# PS.net
KiCad netlist of a schematic drawn in Altium Designer
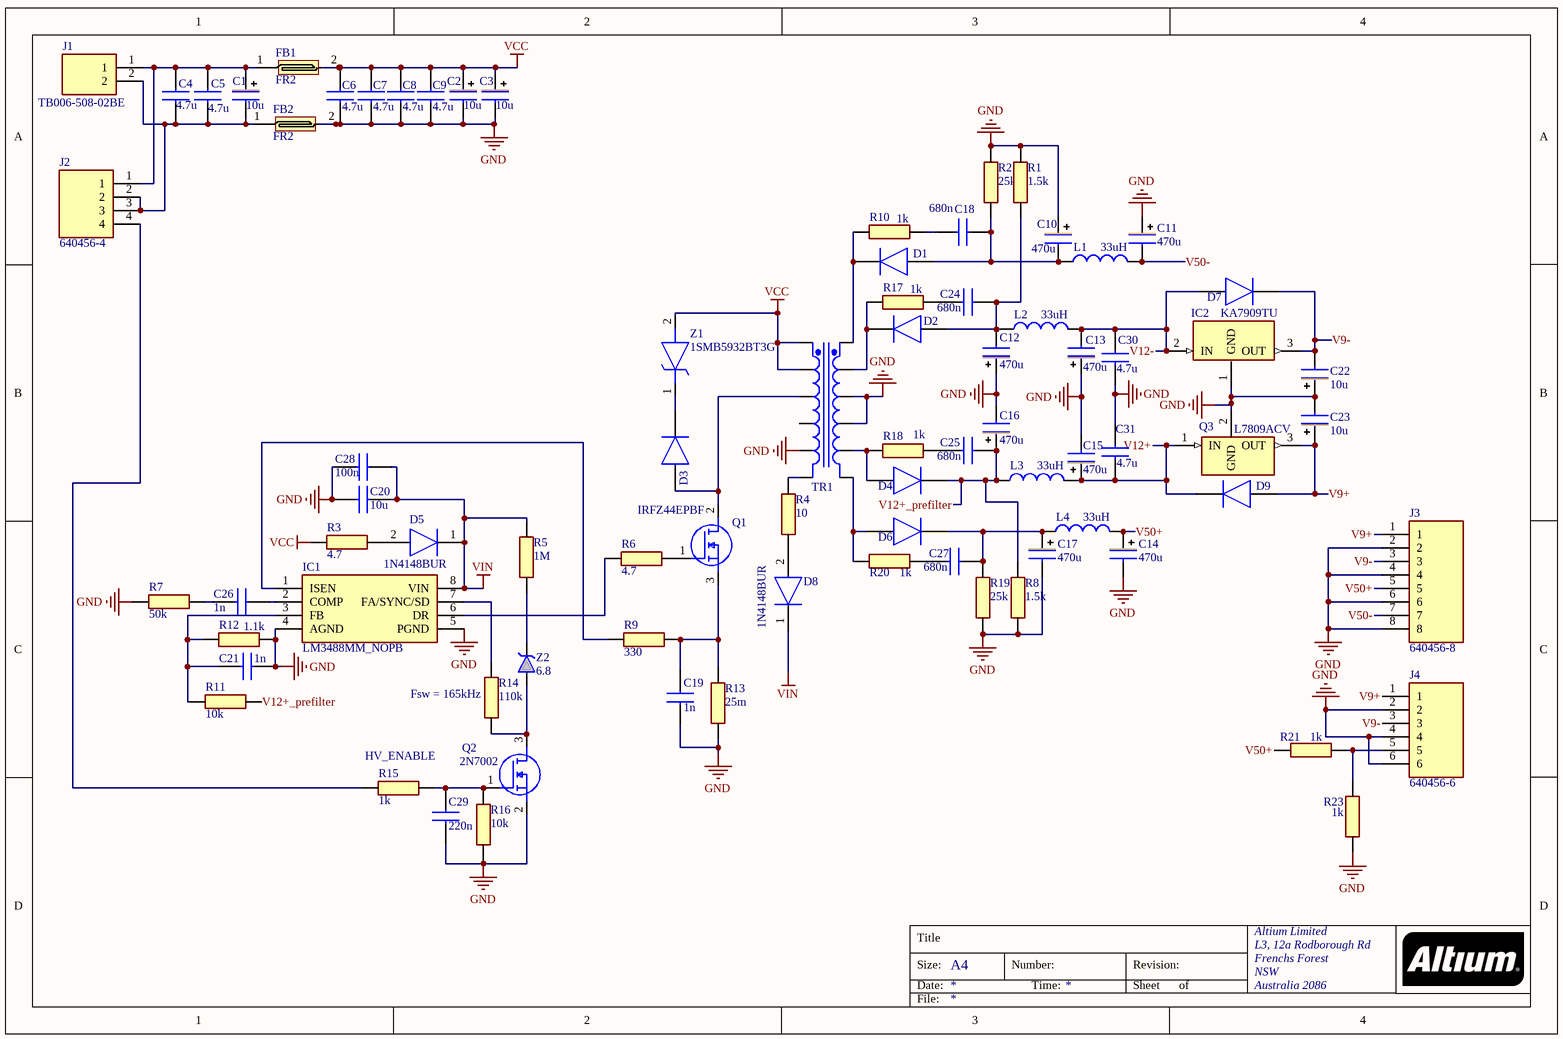
[diagram p0: PS.SchDoc]

(export (version "E")
  (design (tool "Eeschema 10.0.6"))
  (components
    (comp (ref "C1")
      (value "10u")
      (footprint "CapPol8mm")
      (description "Capacitor polarized electrolytic")
      (fields
        (field (name "MANUFACTURER_PART_NUMBER") "B43640A9477M")
        (field (name "MOUSER PART NUMBER") "871-B43640A9477M")
      )
      (libsource (lib "Schlib") (part "CapPol"))
    )
    (comp (ref "C2")
      (value "10u")
      (footprint "CapPol8mm")
      (description "Capacitor polarized electrolytic")
      (fields
        (field (name "MANUFACTURER_PART_NUMBER") "B43640A9477M")
        (field (name "MOUSER PART NUMBER") "871-B43640A9477M")
      )
      (libsource (lib "Schlib") (part "CapPol"))
    )
    (comp (ref "C3")
      (value "10u")
      (footprint "CapPol8mm")
      (description "Capacitor polarized electrolytic")
      (fields
        (field (name "MANUFACTURER_PART_NUMBER") "B43640A9477M")
        (field (name "MOUSER PART NUMBER") "871-B43640A9477M")
      )
      (libsource (lib "Schlib") (part "CapPol"))
    )
    (comp (ref "C4")
      (value "4.7u")
      (footprint "CAPC2012X140N")
      (description "Capacitor smd ceramic")
      (fields
        (field (name "MANUFACTURER_PART_NUMBER") "C3216C0G1H562J060AA")
        (field (name "Comment") "Capacitor_SMD")
      )
      (libsource (lib "Schlib") (part "Capacitor_SMD"))
    )
    (comp (ref "C5")
      (value "4.7u")
      (footprint "CAPC2012X140N")
      (description "Capacitor smd ceramic")
      (fields
        (field (name "MANUFACTURER_PART_NUMBER") "C3216C0G1H562J060AA")
        (field (name "Comment") "Capacitor_SMD")
      )
      (libsource (lib "Schlib") (part "Capacitor_SMD"))
    )
    (comp (ref "C6")
      (value "4.7u")
      (footprint "CAPC2012X140N")
      (description "Capacitor smd ceramic")
      (fields
        (field (name "MANUFACTURER_PART_NUMBER") "C3216C0G1H562J060AA")
        (field (name "Comment") "Capacitor_SMD")
      )
      (libsource (lib "Schlib") (part "Capacitor_SMD"))
    )
    (comp (ref "C7")
      (value "4.7u")
      (footprint "CAPC2012X140N")
      (description "Capacitor smd ceramic")
      (fields
        (field (name "MANUFACTURER_PART_NUMBER") "C3216C0G1H562J060AA")
        (field (name "Comment") "Capacitor_SMD")
      )
      (libsource (lib "Schlib") (part "Capacitor_SMD"))
    )
    (comp (ref "C8")
      (value "4.7u")
      (footprint "CAPC2012X140N")
      (description "Capacitor smd ceramic")
      (fields
        (field (name "MANUFACTURER_PART_NUMBER") "C3216C0G1H562J060AA")
        (field (name "Comment") "Capacitor_SMD")
      )
      (libsource (lib "Schlib") (part "Capacitor_SMD"))
    )
    (comp (ref "C9")
      (value "4.7u")
      (footprint "CAPC2012X140N")
      (description "Capacitor smd ceramic")
      (fields
        (field (name "MANUFACTURER_PART_NUMBER") "C3216C0G1H562J060AA")
        (field (name "Comment") "Capacitor_SMD")
      )
      (libsource (lib "Schlib") (part "Capacitor_SMD"))
    )
    (comp (ref "C10")
      (value "470u")
      (footprint "Cap_pol_5x13")
      (description "Capacitor polarized electrolytic")
      (fields
        (field (name "MANUFACTURER_PART_NUMBER") "B43640A9477M")
        (field (name "MOUSER PART NUMBER") "871-B43640A9477M")
      )
      (libsource (lib "Schlib") (part "CapPol"))
    )
    (comp (ref "C11")
      (value "470u")
      (footprint "Cap_pol_5x13")
      (description "Capacitor polarized electrolytic")
      (fields
        (field (name "MANUFACTURER_PART_NUMBER") "B43640A9477M")
        (field (name "MOUSER PART NUMBER") "871-B43640A9477M")
      )
      (libsource (lib "Schlib") (part "CapPol"))
    )
    (comp (ref "C12")
      (value "470u")
      (footprint "CapPol_D10H16")
      (description "Capacitor polarized electrolytic")
      (fields
        (field (name "MANUFACTURER_PART_NUMBER") "B43640A9477M")
        (field (name "MOUSER PART NUMBER") "871-B43640A9477M")
      )
      (libsource (lib "Schlib") (part "CapPol"))
    )
    (comp (ref "C13")
      (value "470u")
      (footprint "CapPol_D10H16")
      (description "Capacitor polarized electrolytic")
      (fields
        (field (name "MANUFACTURER_PART_NUMBER") "B43640A9477M")
        (field (name "MOUSER PART NUMBER") "871-B43640A9477M")
      )
      (libsource (lib "Schlib") (part "CapPol"))
    )
    (comp (ref "C14")
      (value "470u")
      (footprint "Cap_pol_5x13")
      (description "Capacitor polarized electrolytic")
      (fields
        (field (name "MANUFACTURER_PART_NUMBER") "B43640A9477M")
        (field (name "MOUSER PART NUMBER") "871-B43640A9477M")
      )
      (libsource (lib "Schlib") (part "CapPol"))
    )
    (comp (ref "C15")
      (value "470u")
      (footprint "CapPol_D10H16")
      (description "Capacitor polarized electrolytic")
      (fields
        (field (name "MANUFACTURER_PART_NUMBER") "B43640A9477M")
        (field (name "MOUSER PART NUMBER") "871-B43640A9477M")
      )
      (libsource (lib "Schlib") (part "CapPol"))
    )
    (comp (ref "C16")
      (value "470u")
      (footprint "CapPol_D10H16")
      (description "Capacitor polarized electrolytic")
      (fields
        (field (name "MANUFACTURER_PART_NUMBER") "B43640A9477M")
        (field (name "MOUSER PART NUMBER") "871-B43640A9477M")
      )
      (libsource (lib "Schlib") (part "CapPol"))
    )
    (comp (ref "C17")
      (value "470u")
      (footprint "Cap_pol_5x13")
      (description "Capacitor polarized electrolytic")
      (fields
        (field (name "MANUFACTURER_PART_NUMBER") "B43640A9477M")
        (field (name "MOUSER PART NUMBER") "871-B43640A9477M")
      )
      (libsource (lib "Schlib") (part "CapPol"))
    )
    (comp (ref "C18")
      (value "680n")
      (footprint "CAPC3216X95N")
      (description "Capacitor smd ceramic")
      (fields
        (field (name "MANUFACTURER_PART_NUMBER") "C3216C0G1H562J060AA")
        (field (name "Comment") "Capacitor_SMD")
      )
      (libsource (lib "Schlib") (part "Capacitor_SMD"))
    )
    (comp (ref "C19")
      (value "1n")
      (footprint "CAPC2012X140N")
      (description "Capacitor smd ceramic")
      (fields
        (field (name "MANUFACTURER_PART_NUMBER") "C3216C0G1H562J060AA")
        (field (name "Comment") "Capacitor_SMD")
      )
      (libsource (lib "Schlib") (part "Capacitor_SMD"))
    )
    (comp (ref "C20")
      (value "10u")
      (footprint "CAPC2012X140N")
      (description "Capacitor smd ceramic")
      (fields
        (field (name "MANUFACTURER_PART_NUMBER") "C3216C0G1H562J060AA")
        (field (name "Comment") "Capacitor_SMD")
      )
      (libsource (lib "Schlib") (part "Capacitor_SMD"))
    )
    (comp (ref "C21")
      (value "1n")
      (footprint "CAPC2012X140N")
      (description "Capacitor smd ceramic")
      (fields
        (field (name "MANUFACTURER_PART_NUMBER") "C3216C0G1H562J060AA")
        (field (name "Comment") "Capacitor_SMD")
      )
      (libsource (lib "Schlib") (part "Capacitor_SMD"))
    )
    (comp (ref "C22")
      (value "10u")
      (footprint "CapPol_D10H16")
      (description "Capacitor polarized electrolytic")
      (fields
        (field (name "MANUFACTURER_PART_NUMBER") "B43640A9477M")
        (field (name "MOUSER PART NUMBER") "871-B43640A9477M")
      )
      (libsource (lib "Schlib") (part "CapPol"))
    )
    (comp (ref "C23")
      (value "10u")
      (footprint "CapPol_D10H16")
      (description "Capacitor polarized electrolytic")
      (fields
        (field (name "MANUFACTURER_PART_NUMBER") "B43640A9477M")
        (field (name "MOUSER PART NUMBER") "871-B43640A9477M")
      )
      (libsource (lib "Schlib") (part "CapPol"))
    )
    (comp (ref "C24")
      (value "680n")
      (footprint "CAPC3216X95N")
      (description "Capacitor smd ceramic")
      (fields
        (field (name "MANUFACTURER_PART_NUMBER") "C3216C0G1H562J060AA")
        (field (name "Comment") "Capacitor_SMD")
      )
      (libsource (lib "Schlib") (part "Capacitor_SMD"))
    )
    (comp (ref "C25")
      (value "680n")
      (footprint "CAPC3216X95N")
      (description "Capacitor smd ceramic")
      (fields
        (field (name "MANUFACTURER_PART_NUMBER") "C3216C0G1H562J060AA")
        (field (name "Comment") "Capacitor_SMD")
      )
      (libsource (lib "Schlib") (part "Capacitor_SMD"))
    )
    (comp (ref "C26")
      (value "1n")
      (footprint "CAPC2012X140N")
      (description "Capacitor smd ceramic")
      (fields
        (field (name "MANUFACTURER_PART_NUMBER") "C3216C0G1H562J060AA")
        (field (name "Comment") "Capacitor_SMD")
      )
      (libsource (lib "Schlib") (part "Capacitor_SMD"))
    )
    (comp (ref "C27")
      (value "680n")
      (footprint "CAPC3216X95N")
      (description "Capacitor smd ceramic")
      (fields
        (field (name "MANUFACTURER_PART_NUMBER") "C3216C0G1H562J060AA")
        (field (name "Comment") "Capacitor_SMD")
      )
      (libsource (lib "Schlib") (part "Capacitor_SMD"))
    )
    (comp (ref "C28")
      (value "100n")
      (footprint "CAPC2012X140N")
      (description "Capacitor smd ceramic")
      (fields
        (field (name "MANUFACTURER_PART_NUMBER") "C3216C0G1H562J060AA")
        (field (name "Comment") "Capacitor_SMD")
      )
      (libsource (lib "Schlib") (part "Capacitor_SMD"))
    )
    (comp (ref "C29")
      (value "220n")
      (footprint "CAPC2012X140N")
      (description "Capacitor smd ceramic")
      (fields
        (field (name "MANUFACTURER_PART_NUMBER") "C3216C0G1H562J060AA")
        (field (name "Comment") "Capacitor_SMD")
      )
      (libsource (lib "Schlib") (part "Capacitor_SMD"))
    )
    (comp (ref "C30")
      (value "4.7u")
      (footprint "CAPC3216X95N")
      (description "Capacitor smd ceramic")
      (fields
        (field (name "MANUFACTURER_PART_NUMBER") "C3216C0G1H562J060AA")
        (field (name "Comment") "Capacitor_SMD")
      )
      (libsource (lib "Schlib") (part "Capacitor_SMD"))
    )
    (comp (ref "C31")
      (value "4.7u")
      (footprint "CAPC3216X95N")
      (description "Capacitor smd ceramic")
      (fields
        (field (name "MANUFACTURER_PART_NUMBER") "C3216C0G1H562J060AA")
        (field (name "Comment") "Capacitor_SMD")
      )
      (libsource (lib "Schlib") (part "Capacitor_SMD"))
    )
    (comp (ref "D1")
      (value "SS1200-LTP")
      (footprint "PcbLib:DIOM5226X244N")
      (description "Diode")
      (fields (field (name "MOUSER PART NUMBER") "833-SS1200-LTP"))
      (libsource (lib "Schlib") (part "SS1200-LTP"))
    )
    (comp (ref "D2")
      (value "S2B-13-F")
      (footprint "PcbLib:DIOM5336X250N")
      (description "Diode")
      (fields (field (name "MOUSER PART NUMBER") "621-S2B-F"))
      (libsource (lib "Schlib") (part "S2B-13-F"))
    )
    (comp (ref "D3")
      (value "SS1200-LTP")
      (footprint "PcbLib:DIOM5226X244N")
      (description "Diode")
      (fields (field (name "MOUSER PART NUMBER") "833-SS1200-LTP"))
      (libsource (lib "Schlib") (part "SS1200-LTP"))
    )
    (comp (ref "D4")
      (value "S2B-13-F")
      (footprint "PcbLib:DIOM5336X250N")
      (description "Diode")
      (fields (field (name "MOUSER PART NUMBER") "621-S2B-F"))
      (libsource (lib "Schlib") (part "S2B-13-F"))
    )
    (comp (ref "D5")
      (value "1N4148BUR")
      (footprint "PcbLib:1N4148BUR")
      (description "Diode")
      (libsource (lib "Schlib") (part "1N4148BUR"))
    )
    (comp (ref "D6")
      (value "SS1200-LTP")
      (footprint "PcbLib:DIOM5226X244N")
      (description "Diode")
      (fields (field (name "MOUSER PART NUMBER") "833-SS1200-LTP"))
      (libsource (lib "Schlib") (part "SS1200-LTP"))
    )
    (comp (ref "D7")
      (value "SS1200-LTP")
      (footprint "PcbLib:DIOM5226X244N")
      (description "Diode")
      (fields (field (name "MOUSER PART NUMBER") "833-SS1200-LTP"))
      (libsource (lib "Schlib") (part "SS1200-LTP"))
    )
    (comp (ref "D8")
      (value "1N4148BUR")
      (footprint "PcbLib:1N4148BUR")
      (description "Diode")
      (libsource (lib "Schlib") (part "1N4148BUR"))
    )
    (comp (ref "D9")
      (value "SS1200-LTP")
      (footprint "PcbLib:DIOM5226X244N")
      (description "Diode")
      (fields (field (name "MOUSER PART NUMBER") "833-SS1200-LTP"))
      (libsource (lib "Schlib") (part "SS1200-LTP"))
    )
    (comp (ref "FB1")
      (value "FR2")
      (footprint "FB2")
      (description "THT ferrite bead")
      (libsource (lib "Schlib") (part "FR2"))
    )
    (comp (ref "FB2")
      (value "FR2")
      (footprint "FB2")
      (description "THT ferrite bead")
      (libsource (lib "Schlib") (part "FR2"))
    )
    (comp (ref "IC1")
      (value "LM3488MM_NOPB")
      (footprint "PcbLib:SOP65P490X110-8N")
      (description "Integrated Circuit")
      (fields
        (field (name "MANUFACTURER_PART_NUMBER") "LM3488MM/NOPB")
        (field (name "MOUSER PART NUMBER") "926-LM3488MM/NOPB")
      )
      (libsource (lib "Schlib") (part "LM3488MM_NOPB"))
    )
    (comp (ref "IC2")
      (value "KA7909TU")
      (footprint "PcbLib:TO254P470X1016X2019-3P")
      (description "Integrated Circuit")
      (fields (field (name "MOUSER PART NUMBER") "512-KA7909TU"))
      (libsource (lib "Schlib") (part "KA7909TU"))
    )
    (comp (ref "J1")
      (value "TB006-508-02BE")
      (footprint "PcbLib:TB00650802BE")
      (description "Connector")
      (fields (field (name "MOUSER PART NUMBER") "490-TB006-508-02BE"))
      (libsource (lib "Schlib") (part "TB006-508-02BE"))
    )
    (comp (ref "J2")
      (value "640456-4")
      (footprint "PcbLib:SHDR4W66P0X254_1X4_1016X572X1041P")
      (description "Connector")
      (fields (field (name "MOUSER PART NUMBER") "571-6404564"))
      (libsource (lib "Schlib") (part "640456-4"))
    )
    (comp (ref "J3")
      (value "640456-8")
      (footprint "PcbLib:SHDR8W66P0X254_1X8_2032X572X1024P")
      (description "Connector")
      (fields (field (name "MOUSER PART NUMBER") "571-6404568"))
      (libsource (lib "Schlib") (part "640456-8"))
    )
    (comp (ref "J4")
      (value "640456-6")
      (footprint "PcbLib:SHDR6W66P0X254_1X6_1524X572X1003P")
      (description "Connector")
      (fields (field (name "MOUSER PART NUMBER") "571-6404566"))
      (libsource (lib "Schlib") (part "640456-6"))
    )
    (comp (ref "L1")
      (value "33uH")
      (footprint "TYA3015150M")
      (description "Inductor")
      (fields (field (name "PUBLISHER") "Altium Limited"))
      (libsource (lib "Miscellaneous Devices") (part "Inductor"))
    )
    (comp (ref "L2")
      (value "33uH")
      (footprint "TYA3015150M")
      (description "Inductor")
      (fields (field (name "PUBLISHER") "Altium Limited"))
      (libsource (lib "Miscellaneous Devices") (part "Inductor"))
    )
    (comp (ref "L3")
      (value "33uH")
      (footprint "TYA3015150M")
      (description "Inductor")
      (fields (field (name "PUBLISHER") "Altium Limited"))
      (libsource (lib "Miscellaneous Devices") (part "Inductor"))
    )
    (comp (ref "L4")
      (value "33uH")
      (footprint "TYA3015150M")
      (description "Inductor")
      (fields (field (name "PUBLISHER") "Altium Limited"))
      (libsource (lib "Miscellaneous Devices") (part "Inductor"))
    )
    (comp (ref "Q1")
      (value "IRFZ44EPBF")
      (footprint "PcbLib:TO254P469X1042X1967-3P")
      (description "MOSFET (N-Channel)")
      (fields (field (name "MOUSER PART NUMBER") "942-IRFZ44EPBF"))
      (libsource (lib "Schlib") (part "IRFZ44EPBF"))
    )
    (comp (ref "Q2")
      (value "2N7002")
      (footprint "PcbLib:SOT96P240X120-3N")
      (description "MOSFET (N-Channel)")
      (fields (field (name "MOUSER PART NUMBER") "781-2N7002"))
      (libsource (lib "Schlib") (part "2N7002"))
    )
    (comp (ref "Q3")
      (value "L7809ACV")
      (footprint "PcbLib:TO255P460X1020X2030-3P")
      (description "Transistor")
      (fields (field (name "MOUSER PART NUMBER") "511-L7809ACV"))
      (libsource (lib "Schlib") (part "L7809ACV"))
    )
    (comp (ref "R1")
      (value "1.5k")
      (footprint "PcbLib:RESC3216X75N")
      (description "Resistor SMD")
      (fields
        (field (name "MANUFACTURER_PART_NUMBER") "CR1206-FW-1504ELF")
        (field (name "MOUSER PART NUMBER") "652-CR1206FW1504ELF")
      )
      (libsource (lib "") (part "Res_SMD_1"))
    )
    (comp (ref "R2")
      (value "25k")
      (footprint "PcbLib:RESC3216X75N")
      (description "Resistor SMD")
      (fields
        (field (name "MANUFACTURER_PART_NUMBER") "CR1206-FW-1504ELF")
        (field (name "MOUSER PART NUMBER") "652-CR1206FW1504ELF")
      )
      (libsource (lib "") (part "Res_SMD_1"))
    )
    (comp (ref "R3")
      (value "4.7")
      (footprint "RESC2012X60N")
      (description "Resistor SMD")
      (fields
        (field (name "MANUFACTURER_PART_NUMBER") "CR1206-FW-1504ELF")
        (field (name "MOUSER PART NUMBER") "652-CR1206FW1504ELF")
      )
      (libsource (lib "Schlib") (part "Res_SMD"))
    )
    (comp (ref "R4")
      (value "10")
      (footprint "RESC2012X60N")
      (description "Resistor SMD")
      (fields
        (field (name "MANUFACTURER_PART_NUMBER") "CR1206-FW-1504ELF")
        (field (name "MOUSER PART NUMBER") "652-CR1206FW1504ELF")
      )
      (libsource (lib "") (part "Res_SMD_1"))
    )
    (comp (ref "R5")
      (value "1M")
      (footprint "RESC2012X60N")
      (description "Resistor SMD")
      (fields
        (field (name "MANUFACTURER_PART_NUMBER") "CR1206-FW-1504ELF")
        (field (name "MOUSER PART NUMBER") "652-CR1206FW1504ELF")
      )
      (libsource (lib "") (part "Res_SMD_1"))
    )
    (comp (ref "R6")
      (value "4.7")
      (footprint "RESC2012X60N")
      (description "Resistor SMD")
      (fields
        (field (name "MANUFACTURER_PART_NUMBER") "CR1206-FW-1504ELF")
        (field (name "MOUSER PART NUMBER") "652-CR1206FW1504ELF")
      )
      (libsource (lib "") (part "Res_SMD_3"))
    )
    (comp (ref "R7")
      (value "50k")
      (footprint "RESC2012X60N")
      (description "Resistor SMD")
      (fields
        (field (name "MANUFACTURER_PART_NUMBER") "CR1206-FW-1504ELF")
        (field (name "MOUSER PART NUMBER") "652-CR1206FW1504ELF")
      )
      (libsource (lib "") (part "Res_SMD_3"))
    )
    (comp (ref "R8")
      (value "1.5k")
      (footprint "PcbLib:RESC3216X75N")
      (description "Resistor SMD")
      (fields
        (field (name "MANUFACTURER_PART_NUMBER") "CR1206-FW-1504ELF")
        (field (name "MOUSER PART NUMBER") "652-CR1206FW1504ELF")
      )
      (libsource (lib "") (part "Res_SMD_1"))
    )
    (comp (ref "R9")
      (value "330")
      (footprint "RESC2012X60N")
      (description "Resistor SMD")
      (fields
        (field (name "MANUFACTURER_PART_NUMBER") "CR1206-FW-1504ELF")
        (field (name "MOUSER PART NUMBER") "652-CR1206FW1504ELF")
      )
      (libsource (lib "") (part "Res_SMD_3"))
    )
    (comp (ref "R10")
      (value "1k")
      (footprint "RESC5025X65N")
      (description "Resistor SMD")
      (fields
        (field (name "MANUFACTURER_PART_NUMBER") "CR1206-FW-1504ELF")
        (field (name "MOUSER PART NUMBER") "652-CR1206FW1504ELF")
      )
      (libsource (lib "Schlib") (part "Res_SMD"))
    )
    (comp (ref "R11")
      (value "10k")
      (footprint "RESC2012X60N")
      (description "Resistor SMD")
      (fields
        (field (name "MANUFACTURER_PART_NUMBER") "CR1206-FW-1504ELF")
        (field (name "MOUSER PART NUMBER") "652-CR1206FW1504ELF")
      )
      (libsource (lib "") (part "Res_SMD_3"))
    )
    (comp (ref "R12")
      (value "1.1k")
      (footprint "RESC2012X60N")
      (description "Resistor SMD")
      (fields
        (field (name "MANUFACTURER_PART_NUMBER") "CR1206-FW-1504ELF")
        (field (name "MOUSER PART NUMBER") "652-CR1206FW1504ELF")
      )
      (libsource (lib "Schlib") (part "Res_SMD"))
    )
    (comp (ref "R13")
      (value "25m")
      (footprint "RESC6331X75N")
      (description "Resistor SMD")
      (fields
        (field (name "MANUFACTURER_PART_NUMBER") "CR1206-FW-1504ELF")
        (field (name "MOUSER PART NUMBER") "652-CR1206FW1504ELF")
      )
      (libsource (lib "") (part "Res_SMD_1"))
    )
    (comp (ref "R14")
      (value "110k")
      (footprint "RESC2012X60N")
      (description "Resistor SMD")
      (fields
        (field (name "MANUFACTURER_PART_NUMBER") "CR1206-FW-1504ELF")
        (field (name "MOUSER PART NUMBER") "652-CR1206FW1504ELF")
      )
      (libsource (lib "") (part "Res_SMD_1"))
    )
    (comp (ref "R15")
      (value "1k")
      (footprint "RESC2012X60N")
      (description "Resistor SMD")
      (fields
        (field (name "MANUFACTURER_PART_NUMBER") "CR1206-FW-1504ELF")
        (field (name "MOUSER PART NUMBER") "652-CR1206FW1504ELF")
      )
      (libsource (lib "") (part "Res_SMD_3"))
    )
    (comp (ref "R16")
      (value "10k")
      (footprint "RESC2012X60N")
      (description "Resistor SMD")
      (fields
        (field (name "MANUFACTURER_PART_NUMBER") "CR1206-FW-1504ELF")
        (field (name "MOUSER PART NUMBER") "652-CR1206FW1504ELF")
      )
      (libsource (lib "") (part "Res_SMD_1"))
    )
    (comp (ref "R17")
      (value "1k")
      (footprint "RESC5025X65N")
      (description "Resistor SMD")
      (fields
        (field (name "MANUFACTURER_PART_NUMBER") "CR1206-FW-1504ELF")
        (field (name "MOUSER PART NUMBER") "652-CR1206FW1504ELF")
      )
      (libsource (lib "Schlib") (part "Res_SMD"))
    )
    (comp (ref "R18")
      (value "1k")
      (footprint "RESC5025X65N")
      (description "Resistor SMD")
      (fields
        (field (name "MANUFACTURER_PART_NUMBER") "CR1206-FW-1504ELF")
        (field (name "MOUSER PART NUMBER") "652-CR1206FW1504ELF")
      )
      (libsource (lib "Schlib") (part "Res_SMD"))
    )
    (comp (ref "R19")
      (value "25k")
      (footprint "PcbLib:RESC3216X75N")
      (description "Resistor SMD")
      (fields
        (field (name "MANUFACTURER_PART_NUMBER") "CR1206-FW-1504ELF")
        (field (name "MOUSER PART NUMBER") "652-CR1206FW1504ELF")
      )
      (libsource (lib "") (part "Res_SMD_1"))
    )
    (comp (ref "R20")
      (value "1k")
      (footprint "RESC5025X65N")
      (description "Resistor SMD")
      (fields
        (field (name "MANUFACTURER_PART_NUMBER") "CR1206-FW-1504ELF")
        (field (name "MOUSER PART NUMBER") "652-CR1206FW1504ELF")
      )
      (libsource (lib "Schlib") (part "Res_SMD"))
    )
    (comp (ref "R21")
      (value "1k")
      (footprint "PcbLib:RESC3216X75N")
      (description "Resistor SMD")
      (fields
        (field (name "MANUFACTURER_PART_NUMBER") "CR1206-FW-1504ELF")
        (field (name "MOUSER PART NUMBER") "652-CR1206FW1504ELF")
      )
      (libsource (lib "Schlib") (part "Res_SMD"))
    )
    (comp (ref "R23")
      (value "1k")
      (footprint "PcbLib:RESC3216X75N")
      (description "Resistor SMD")
      (fields
        (field (name "MANUFACTURER_PART_NUMBER") "CR1206-FW-1504ELF")
        (field (name "MOUSER PART NUMBER") "652-CR1206FW1504ELF")
      )
      (libsource (lib "") (part "Res_SMD_2"))
    )
    (comp (ref "TR1")
      (value "Transformer 12pin30.15.7")
      (footprint "TRAFO5mmX25mm12pcs")
      (description "Transformer EE 30x15x7 WxHxL 12pin")
      (libsource (lib "Schlib") (part "Transformer 12pin30.15.7"))
    )
    (comp (ref "Z1")
      (value "1SMB5932BT3G")
      (footprint "PcbLib:DIOM5436X247N")
      (description "Zener Diode")
      (fields (field (name "MOUSER PART NUMBER") "863-1SMB5932BT3G"))
      (libsource (lib "*") (part "1SMB5932BT3G"))
    )
    (comp (ref "Z2")
      (value "6.8")
      (footprint "SOD-80")
      (description "Zener Diode")
      (fields
        (field (name "MANUFACTURER_PART_NUMBER") "GLL4739-E3/97")
        (field (name "MOUSER PART NUMBER") "78-GLL4739-E3/97")
      )
      (libsource (lib "Schlib") (part "Zener"))
    )
  )
  (nets
    (net (code "1") (name "/V9+") (class "Default")
      (node (ref "C23") (pin "1") (pinfunction "+_1") (pintype "passive"))
      (node (ref "D9") (pin "2") (pinfunction "A_2") (pintype "passive"))
      (node (ref "J3") (pin "1") (pinfunction "1_1") (pintype "passive"))
      (node (ref "J4") (pin "1") (pinfunction "1_1") (pintype "passive"))
      (node (ref "Q3") (pin "3") (pinfunction "OUT_3") (pintype "output"))
    )
    (net (code "2") (name "/V9-") (class "Default")
      (node (ref "C22") (pin "2") (pinfunction "-_2") (pintype "passive"))
      (node (ref "D7") (pin "1") (pinfunction "K_1") (pintype "passive"))
      (node (ref "IC2") (pin "3") (pinfunction "OUT_3") (pintype "output"))
      (node (ref "J3") (pin "3") (pinfunction "3_3") (pintype "passive"))
      (node (ref "J4") (pin "3") (pinfunction "3_3") (pintype "passive"))
    )
    (net (code "3") (name "/V12+") (class "Default")
      (node (ref "C15") (pin "1") (pinfunction "+_1") (pintype "passive"))
      (node (ref "C31") (pin "1") (pinfunction "1_1") (pintype "passive"))
      (node (ref "D9") (pin "1") (pinfunction "K_1") (pintype "passive"))
      (node (ref "L3") (pin "2") (pinfunction "2_2") (pintype "passive"))
      (node (ref "Q3") (pin "1") (pinfunction "IN_1") (pintype "input"))
    )
    (net (code "4") (name "/V12+_prefilter") (class "Default")
      (node (ref "C16") (pin "1") (pinfunction "+_1") (pintype "passive"))
      (node (ref "C25") (pin "1") (pinfunction "1_1") (pintype "passive"))
      (node (ref "D4") (pin "1") (pinfunction "K_1") (pintype "passive"))
      (node (ref "L3") (pin "1") (pinfunction "1_1") (pintype "passive"))
      (node (ref "R11") (pin "2") (pinfunction "2_2") (pintype "passive"))
      (node (ref "R8") (pin "2") (pinfunction "2_2") (pintype "passive"))
    )
    (net (code "5") (name "/V12-") (class "Default")
      (node (ref "C13") (pin "2") (pinfunction "-_2") (pintype "passive"))
      (node (ref "C30") (pin "2") (pinfunction "2_2") (pintype "passive"))
      (node (ref "D7") (pin "2") (pinfunction "A_2") (pintype "passive"))
      (node (ref "IC2") (pin "2") (pinfunction "IN_2") (pintype "input"))
      (node (ref "L2") (pin "2") (pinfunction "2_2") (pintype "passive"))
    )
    (net (code "6") (name "/V50+") (class "Default")
      (node (ref "C14") (pin "1") (pinfunction "+_1") (pintype "passive"))
      (node (ref "J3") (pin "5") (pinfunction "5_5") (pintype "passive"))
      (node (ref "L4") (pin "2") (pinfunction "2_2") (pintype "passive"))
      (node (ref "R21") (pin "2") (pinfunction "2_2") (pintype "passive"))
    )
    (net (code "7") (name "/V50-") (class "Default")
      (node (ref "C11") (pin "2") (pinfunction "-_2") (pintype "passive"))
      (node (ref "J3") (pin "7") (pinfunction "7_7") (pintype "passive"))
      (node (ref "L1") (pin "2") (pinfunction "2_2") (pintype "passive"))
    )
    (net (code "8") (name "GND") (class "Default")
      (node (ref "C10") (pin "1") (pinfunction "+_1") (pintype "passive"))
      (node (ref "C11") (pin "1") (pinfunction "+_1") (pintype "passive"))
      (node (ref "C12") (pin "1") (pinfunction "+_1") (pintype "passive"))
      (node (ref "C13") (pin "1") (pinfunction "+_1") (pintype "passive"))
      (node (ref "C14") (pin "2") (pinfunction "-_2") (pintype "passive"))
      (node (ref "C15") (pin "2") (pinfunction "-_2") (pintype "passive"))
      (node (ref "C16") (pin "2") (pinfunction "-_2") (pintype "passive"))
      (node (ref "C17") (pin "2") (pinfunction "-_2") (pintype "passive"))
      (node (ref "C19") (pin "1") (pinfunction "1_1") (pintype "passive"))
      (node (ref "C2") (pin "2") (pinfunction "-_2") (pintype "passive"))
      (node (ref "C20") (pin "1") (pinfunction "1_1") (pintype "passive"))
      (node (ref "C21") (pin "2") (pinfunction "2_2") (pintype "passive"))
      (node (ref "C22") (pin "1") (pinfunction "+_1") (pintype "passive"))
      (node (ref "C23") (pin "2") (pinfunction "-_2") (pintype "passive"))
      (node (ref "C28") (pin "1") (pinfunction "1_1") (pintype "passive"))
      (node (ref "C29") (pin "1") (pinfunction "1_1") (pintype "passive"))
      (node (ref "C3") (pin "2") (pinfunction "-_2") (pintype "passive"))
      (node (ref "C30") (pin "1") (pinfunction "1_1") (pintype "passive"))
      (node (ref "C31") (pin "2") (pinfunction "2_2") (pintype "passive"))
      (node (ref "C6") (pin "1") (pinfunction "1_1") (pintype "passive"))
      (node (ref "C7") (pin "1") (pinfunction "1_1") (pintype "passive"))
      (node (ref "C8") (pin "1") (pinfunction "1_1") (pintype "passive"))
      (node (ref "C9") (pin "1") (pinfunction "1_1") (pintype "passive"))
      (node (ref "FB2") (pin "2") (pinfunction "2_2") (pintype "passive"))
      (node (ref "IC1") (pin "4") (pinfunction "AGND_4") (pintype "passive"))
      (node (ref "IC1") (pin "5") (pinfunction "PGND_5") (pintype "passive"))
      (node (ref "IC2") (pin "1") (pinfunction "GND_1") (pintype "passive"))
      (node (ref "J3") (pin "2") (pinfunction "2_2") (pintype "passive"))
      (node (ref "J3") (pin "4") (pinfunction "4_4") (pintype "passive"))
      (node (ref "J3") (pin "6") (pinfunction "6_6") (pintype "passive"))
      (node (ref "J3") (pin "8") (pinfunction "8_8") (pintype "passive"))
      (node (ref "J4") (pin "2") (pinfunction "2_2") (pintype "passive"))
      (node (ref "J4") (pin "4") (pinfunction "4_4") (pintype "passive"))
      (node (ref "J4") (pin "6") (pinfunction "6_6") (pintype "passive"))
      (node (ref "Q2") (pin "2") (pinfunction "S_2") (pintype "passive"))
      (node (ref "Q3") (pin "2") (pinfunction "GND_2") (pintype "power_in"))
      (node (ref "R1") (pin "2") (pinfunction "2_2") (pintype "passive"))
      (node (ref "R12") (pin "1") (pinfunction "1_1") (pintype "passive"))
      (node (ref "R13") (pin "1") (pinfunction "1_1") (pintype "passive"))
      (node (ref "R16") (pin "1") (pinfunction "1_1") (pintype "passive"))
      (node (ref "R19") (pin "1") (pinfunction "1_1") (pintype "passive"))
      (node (ref "R2") (pin "2") (pinfunction "2_2") (pintype "passive"))
      (node (ref "R23") (pin "2") (pinfunction "2_2") (pintype "passive"))
      (node (ref "R7") (pin "1") (pinfunction "1_1") (pintype "passive"))
      (node (ref "R8") (pin "1") (pinfunction "1_1") (pintype "passive"))
      (node (ref "TR1") (pin "10") (pintype "passive"))
      (node (ref "TR1") (pin "5") (pintype "passive"))
      (node (ref "TR1") (pin "9") (pintype "passive"))
    )
    (net (code "9") (name "Net-(C1-+)") (class "Default")
      (node (ref "C1") (pin "1") (pinfunction "+_1") (pintype "passive"))
      (node (ref "C4") (pin "2") (pinfunction "2_2") (pintype "passive"))
      (node (ref "C5") (pin "2") (pinfunction "2_2") (pintype "passive"))
      (node (ref "FB1") (pin "1") (pinfunction "1_1") (pintype "passive"))
      (node (ref "J1") (pin "1") (pinfunction "1_1") (pintype "passive"))
      (node (ref "J2") (pin "1") (pinfunction "1_1") (pintype "passive"))
    )
    (net (code "10") (name "Net-(C1--)") (class "Default")
      (node (ref "C1") (pin "2") (pinfunction "-_2") (pintype "passive"))
      (node (ref "C4") (pin "1") (pinfunction "1_1") (pintype "passive"))
      (node (ref "C5") (pin "1") (pinfunction "1_1") (pintype "passive"))
      (node (ref "FB2") (pin "1") (pinfunction "1_1") (pintype "passive"))
      (node (ref "J1") (pin "2") (pinfunction "2_2") (pintype "passive"))
      (node (ref "J2") (pin "2") (pinfunction "2_2") (pintype "passive"))
      (node (ref "J2") (pin "3") (pinfunction "3_3") (pintype "passive"))
    )
    (net (code "11") (name "Net-(C10--)") (class "Default")
      (node (ref "C10") (pin "2") (pinfunction "-_2") (pintype "passive"))
      (node (ref "C18") (pin "1") (pinfunction "1_1") (pintype "passive"))
      (node (ref "D1") (pin "2") (pinfunction "A_2") (pintype "passive"))
      (node (ref "L1") (pin "1") (pinfunction "1_1") (pintype "passive"))
      (node (ref "R2") (pin "1") (pinfunction "1_1") (pintype "passive"))
    )
    (net (code "12") (name "Net-(C12--)") (class "Default")
      (node (ref "C12") (pin "2") (pinfunction "-_2") (pintype "passive"))
      (node (ref "C24") (pin "1") (pinfunction "1_1") (pintype "passive"))
      (node (ref "D2") (pin "2") (pinfunction "A_2") (pintype "passive"))
      (node (ref "L2") (pin "1") (pinfunction "1_1") (pintype "passive"))
      (node (ref "R1") (pin "1") (pinfunction "1_1") (pintype "passive"))
    )
    (net (code "13") (name "Net-(C17-+)") (class "Default")
      (node (ref "C17") (pin "1") (pinfunction "+_1") (pintype "passive"))
      (node (ref "C27") (pin "2") (pinfunction "2_2") (pintype "passive"))
      (node (ref "D6") (pin "1") (pinfunction "K_1") (pintype "passive"))
      (node (ref "L4") (pin "1") (pinfunction "1_1") (pintype "passive"))
      (node (ref "R19") (pin "2") (pinfunction "2_2") (pintype "passive"))
    )
    (net (code "14") (name "Net-(C18-Pad2)") (class "Default")
      (node (ref "C18") (pin "2") (pinfunction "2_2") (pintype "passive"))
      (node (ref "R10") (pin "1") (pinfunction "1_1") (pintype "passive"))
    )
    (net (code "15") (name "Net-(C24-Pad2)") (class "Default")
      (node (ref "C24") (pin "2") (pinfunction "2_2") (pintype "passive"))
      (node (ref "R17") (pin "1") (pinfunction "1_1") (pintype "passive"))
    )
    (net (code "16") (name "Net-(C25-Pad2)") (class "Default")
      (node (ref "C25") (pin "2") (pinfunction "2_2") (pintype "passive"))
      (node (ref "R18") (pin "1") (pinfunction "1_1") (pintype "passive"))
    )
    (net (code "17") (name "Net-(C26-Pad1)") (class "Default")
      (node (ref "C26") (pin "1") (pinfunction "1_1") (pintype "passive"))
      (node (ref "R7") (pin "2") (pinfunction "2_2") (pintype "passive"))
    )
    (net (code "18") (name "Net-(C27-Pad1)") (class "Default")
      (node (ref "C27") (pin "1") (pinfunction "1_1") (pintype "passive"))
      (node (ref "R20") (pin "1") (pinfunction "1_1") (pintype "passive"))
    )
    (net (code "19") (name "Net-(D1-K)") (class "Default")
      (node (ref "D1") (pin "1") (pinfunction "K_1") (pintype "passive"))
      (node (ref "R10") (pin "2") (pinfunction "2_2") (pintype "passive"))
      (node (ref "TR1") (pin "12") (pintype "passive"))
    )
    (net (code "20") (name "Net-(D2-K)") (class "Default")
      (node (ref "D2") (pin "1") (pinfunction "K_1") (pintype "passive"))
      (node (ref "R17") (pin "2") (pinfunction "2_2") (pintype "passive"))
      (node (ref "TR1") (pin "11") (pintype "passive"))
    )
    (net (code "21") (name "Net-(D3-A)") (class "Default")
      (node (ref "D3") (pin "2") (pinfunction "A_2") (pintype "passive"))
      (node (ref "Q1") (pin "2") (pinfunction "D_2") (pintype "passive"))
      (node (ref "TR1") (pin "3") (pintype "passive"))
    )
    (net (code "22") (name "Net-(D3-K)") (class "Default")
      (node (ref "D3") (pin "1") (pinfunction "K_1") (pintype "passive"))
      (node (ref "Z1") (pin "1") (pinfunction "K_1") (pintype "passive"))
    )
    (net (code "23") (name "Net-(D4-A)") (class "Default")
      (node (ref "D4") (pin "2") (pinfunction "A_2") (pintype "passive"))
      (node (ref "R18") (pin "2") (pinfunction "2_2") (pintype "passive"))
      (node (ref "TR1") (pin "8") (pintype "passive"))
    )
    (net (code "24") (name "Net-(D5-A)") (class "Default")
      (node (ref "D5") (pin "2") (pinfunction "A_2") (pintype "passive"))
      (node (ref "R3") (pin "1") (pinfunction "1_1") (pintype "passive"))
    )
    (net (code "25") (name "Net-(D6-A)") (class "Default")
      (node (ref "D6") (pin "2") (pinfunction "A_2") (pintype "passive"))
      (node (ref "R20") (pin "2") (pinfunction "2_2") (pintype "passive"))
      (node (ref "TR1") (pin "7") (pintype "passive"))
    )
    (net (code "26") (name "Net-(D8-A)") (class "Default")
      (node (ref "D8") (pin "2") (pinfunction "A_2") (pintype "passive"))
      (node (ref "R4") (pin "1") (pinfunction "1_1") (pintype "passive"))
    )
    (net (code "27") (name "Net-(IC1-COMP)") (class "Default")
      (node (ref "C26") (pin "2") (pinfunction "2_2") (pintype "passive"))
      (node (ref "IC1") (pin "2") (pinfunction "COMP_2") (pintype "passive"))
    )
    (net (code "28") (name "Net-(IC1-DR)") (class "Default")
      (node (ref "IC1") (pin "6") (pinfunction "DR_6") (pintype "passive"))
      (node (ref "R6") (pin "1") (pinfunction "1_1") (pintype "passive"))
    )
    (net (code "29") (name "Net-(IC1-FA{slash}SYNC{slash}SD)") (class "Default")
      (node (ref "IC1") (pin "7") (pinfunction "FA/SYNC/SD_7") (pintype "passive"))
      (node (ref "R14") (pin "2") (pinfunction "2_2") (pintype "passive"))
    )
    (net (code "30") (name "Net-(IC1-FB)") (class "Default")
      (node (ref "C21") (pin "1") (pinfunction "1_1") (pintype "passive"))
      (node (ref "IC1") (pin "3") (pinfunction "FB_3") (pintype "passive"))
      (node (ref "R11") (pin "1") (pinfunction "1_1") (pintype "passive"))
      (node (ref "R12") (pin "2") (pinfunction "2_2") (pintype "passive"))
    )
    (net (code "31") (name "Net-(IC1-ISEN)") (class "Default")
      (node (ref "IC1") (pin "1") (pinfunction "ISEN_1") (pintype "passive"))
      (node (ref "R9") (pin "1") (pinfunction "1_1") (pintype "passive"))
    )
    (net (code "32") (name "Net-(J2-Pad4)") (class "Default")
      (node (ref "J2") (pin "4") (pinfunction "4_4") (pintype "passive"))
      (node (ref "R15") (pin "1") (pinfunction "1_1") (pintype "passive"))
    )
    (net (code "33") (name "Net-(J4-Pad5)") (class "Default")
      (node (ref "J4") (pin "5") (pinfunction "5_5") (pintype "passive"))
      (node (ref "R21") (pin "1") (pinfunction "1_1") (pintype "passive"))
      (node (ref "R23") (pin "1") (pinfunction "1_1") (pintype "passive"))
    )
    (net (code "34") (name "Net-(Q1-G)") (class "Default")
      (node (ref "Q1") (pin "1") (pinfunction "G_1") (pintype "passive"))
      (node (ref "R6") (pin "2") (pinfunction "2_2") (pintype "passive"))
    )
    (net (code "35") (name "Net-(Q1-S)") (class "Default")
      (node (ref "C19") (pin "2") (pinfunction "2_2") (pintype "passive"))
      (node (ref "Q1") (pin "3") (pinfunction "S_3") (pintype "passive"))
      (node (ref "R13") (pin "2") (pinfunction "2_2") (pintype "passive"))
      (node (ref "R9") (pin "2") (pinfunction "2_2") (pintype "passive"))
    )
    (net (code "36") (name "Net-(Q2-D)") (class "Default")
      (node (ref "Q2") (pin "3") (pinfunction "D_3") (pintype "passive"))
      (node (ref "R14") (pin "1") (pinfunction "1_1") (pintype "passive"))
      (node (ref "Z2") (pin "2") (pinfunction "A_2") (pintype "passive"))
    )
    (net (code "37") (name "Net-(Q2-G)") (class "Default")
      (node (ref "C29") (pin "2") (pinfunction "2_2") (pintype "passive"))
      (node (ref "Q2") (pin "1") (pinfunction "G_1") (pintype "passive"))
      (node (ref "R15") (pin "2") (pinfunction "2_2") (pintype "passive"))
      (node (ref "R16") (pin "2") (pinfunction "2_2") (pintype "passive"))
    )
    (net (code "38") (name "Net-(R4-Pad2)") (class "Default")
      (node (ref "R4") (pin "2") (pinfunction "2_2") (pintype "passive"))
      (node (ref "TR1") (pin "6") (pintype "passive"))
    )
    (net (code "39") (name "Net-(Z2-K)") (class "Default")
      (node (ref "R5") (pin "1") (pinfunction "1_1") (pintype "passive"))
      (node (ref "Z2") (pin "1") (pinfunction "K_1") (pintype "passive"))
    )
    (net (code "40") (name "VCC") (class "Default")
      (node (ref "C2") (pin "1") (pinfunction "+_1") (pintype "passive"))
      (node (ref "C3") (pin "1") (pinfunction "+_1") (pintype "passive"))
      (node (ref "C6") (pin "2") (pinfunction "2_2") (pintype "passive"))
      (node (ref "C7") (pin "2") (pinfunction "2_2") (pintype "passive"))
      (node (ref "C8") (pin "2") (pinfunction "2_2") (pintype "passive"))
      (node (ref "C9") (pin "2") (pinfunction "2_2") (pintype "passive"))
      (node (ref "FB1") (pin "2") (pinfunction "2_2") (pintype "passive"))
      (node (ref "R3") (pin "2") (pinfunction "2_2") (pintype "passive"))
      (node (ref "TR1") (pin "1") (pintype "passive"))
      (node (ref "TR1") (pin "2") (pintype "passive"))
      (node (ref "Z1") (pin "2") (pinfunction "A_2") (pintype "passive"))
    )
    (net (code "41") (name "VIN") (class "Default")
      (node (ref "C20") (pin "2") (pinfunction "2_2") (pintype "passive"))
      (node (ref "C28") (pin "2") (pinfunction "2_2") (pintype "passive"))
      (node (ref "D5") (pin "1") (pinfunction "K_1") (pintype "passive"))
      (node (ref "D8") (pin "1") (pinfunction "K_1") (pintype "passive"))
      (node (ref "IC1") (pin "8") (pinfunction "VIN_8") (pintype "passive"))
      (node (ref "R5") (pin "2") (pinfunction "2_2") (pintype "passive"))
    )
    (net (code "42") (name "unconnected-(TR1-Pad4)") (class "Default")
      (node (ref "TR1") (pin "4") (pintype "passive"))
    )
  )
)
